# ics-41350-breakout.net
KiCad netlist of a schematic drawn in EAGLE
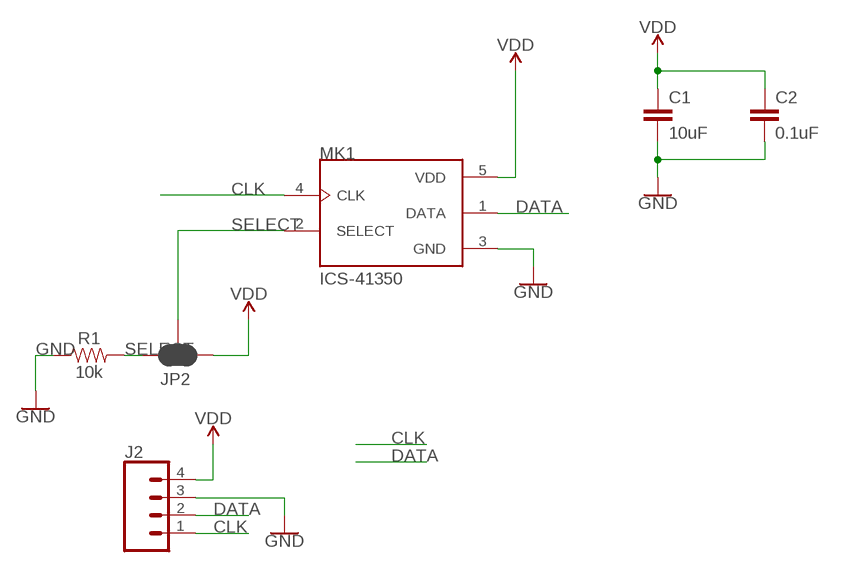
[diagram p0: schematic, sheet 1]

(export (version "E")
  (design (tool "Eeschema 10.0.6"))
  (components
    (comp (ref "C1")
      (value "10uF")
      (footprint "eagle-import:0805")
      (libsource (lib "eagle-import") (part "10UF-0805-10V-10%"))
    )
    (comp (ref "C2")
      (value "0.1uF")
      (footprint "eagle-import:0603")
      (libsource (lib "eagle-import") (part "0.1UF-0603-25V-(+80/-20%)"))
    )
    (comp (ref "J2")
      (value "CONN_041X04_NO_SILK")
      (footprint "eagle-import:1X04_NO_SILK")
      (libsource (lib "eagle-import") (part "CONN_041X04_NO_SILK"))
    )
    (comp (ref "JP2")
      (value "JUMPER-SMT_3_2-NC_PASTE_SILK")
      (footprint "eagle-import:SMT-JUMPER_3_2-NC_PASTE_SILK")
      (libsource (lib "eagle-import") (part "JUMPER-SMT_3_2-NC_PASTE_SILK"))
    )
    (comp (ref "MK1")
      (value "ICS-41350")
      (footprint "eagle-import:MIC_ICS-41350")
      (fields (field (name "DIGI-KEY_PART_NUMBER") "1428-1064-1-ND") (field (name "MF") "TDK InvenSense"))
      (libsource (lib "eagle-import") (part "ICS-41350"))
    )
    (comp (ref "R1")
      (value "10k")
      (footprint "eagle-import:0603")
      (libsource (lib "eagle-import") (part "10KOHM-0603-1/10W-1%"))
    )
  )
  (nets
    (net (code "1") (name "/CLK") (class "Default")
      (node (ref "J2") (pin "1") (pinfunction "1_1") (pintype "passive"))
      (node (ref "MK1") (pin "4") (pinfunction "CLK_4") (pintype "input"))
    )
    (net (code "2") (name "/DATA") (class "Default")
      (node (ref "J2") (pin "2") (pinfunction "2_2") (pintype "passive"))
      (node (ref "MK1") (pin "1") (pinfunction "DATA_1") (pintype "output"))
    )
    (net (code "3") (name "/SELECT") (class "Default")
      (node (ref "JP2") (pin "2") (pinfunction "2_2") (pintype "passive"))
      (node (ref "JP2") (pin "3") (pinfunction "3_3") (pintype "passive"))
      (node (ref "MK1") (pin "2") (pinfunction "SELECT_2") (pintype "input"))
      (node (ref "R1") (pin "2") (pinfunction "2_2") (pintype "passive"))
    )
    (net (code "4") (name "GND") (class "Default")
      (node (ref "C1") (pin "2") (pinfunction "2_2") (pintype "passive"))
      (node (ref "C2") (pin "2") (pinfunction "2_2") (pintype "passive"))
      (node (ref "J2") (pin "3") (pinfunction "3_3") (pintype "passive"))
      (node (ref "MK1") (pin "3") (pinfunction "GND_3") (pintype "power_in"))
      (node (ref "R1") (pin "1") (pinfunction "1_1") (pintype "passive"))
    )
    (net (code "5") (name "VDD") (class "Default")
      (node (ref "C1") (pin "1") (pinfunction "1_1") (pintype "passive"))
      (node (ref "C2") (pin "1") (pinfunction "1_1") (pintype "passive"))
      (node (ref "J2") (pin "4") (pinfunction "4_4") (pintype "passive"))
      (node (ref "JP2") (pin "1") (pinfunction "1_1") (pintype "passive"))
      (node (ref "MK1") (pin "5") (pinfunction "VDD_5") (pintype "power_in"))
    )
  )
)
